# 08C-005.net
KiCad netlist of a schematic drawn in EAGLE
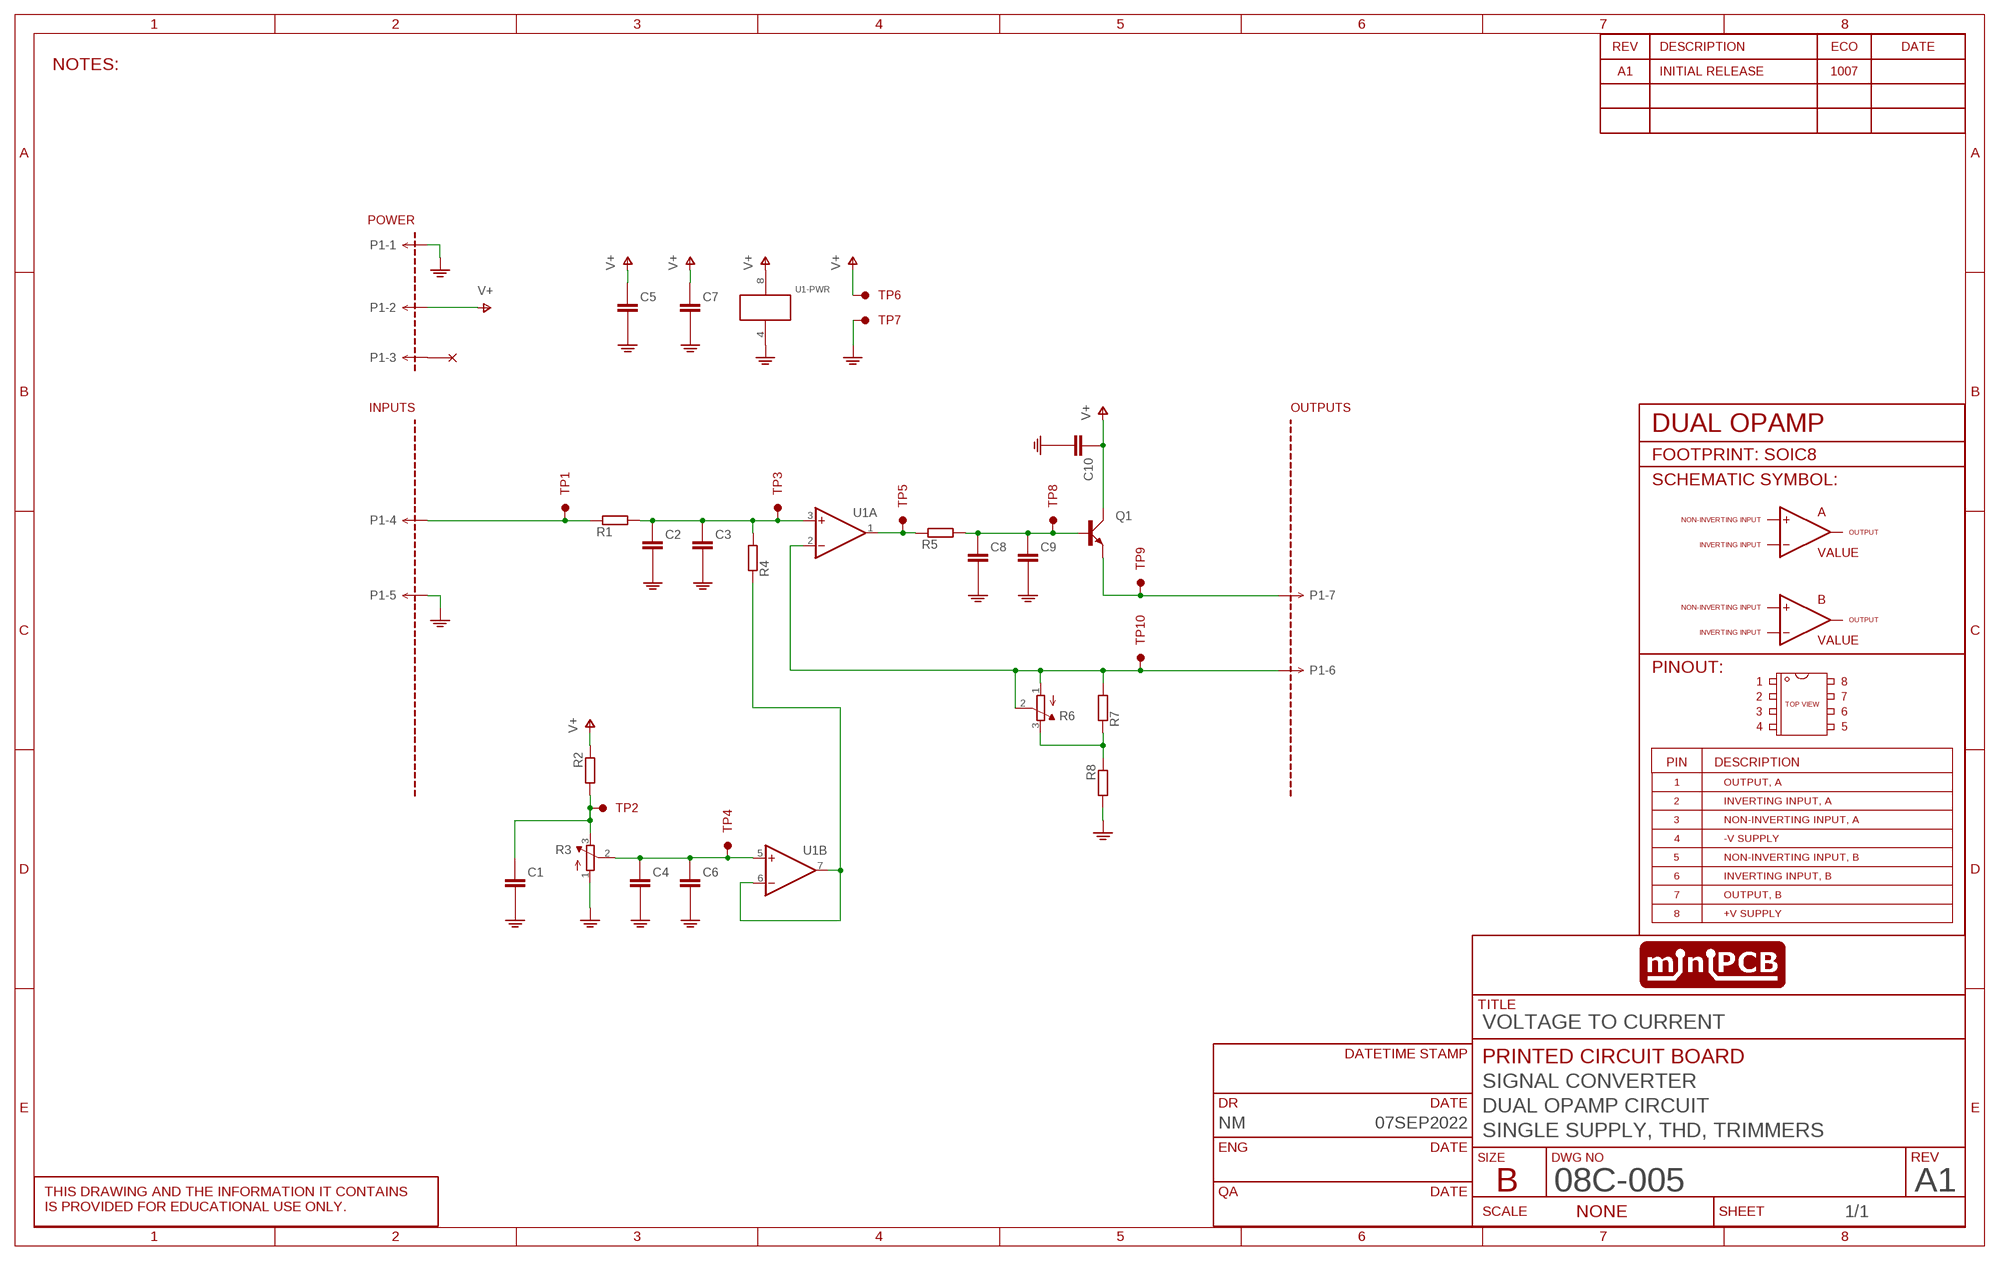
[diagram p0: schematic, sheet 1]

(export (version "E")
  (design (tool "Eeschema 10.0.6"))
  (components
    (comp (ref "C1")
      (value "CAPACITORTHD")
      (footprint "eagle-import:C050-024X044")
      (libsource (lib "eagle-import") (part "CAPACITORTHD"))
    )
    (comp (ref "C2")
      (value "CAPACITORTHD")
      (footprint "eagle-import:C050-024X044")
      (libsource (lib "eagle-import") (part "CAPACITORTHD"))
    )
    (comp (ref "C3")
      (value "CAPACITORTHD")
      (footprint "eagle-import:C050-024X044")
      (libsource (lib "eagle-import") (part "CAPACITORTHD"))
    )
    (comp (ref "C4")
      (value "CAPACITORTHD")
      (footprint "eagle-import:C050-024X044")
      (libsource (lib "eagle-import") (part "CAPACITORTHD"))
    )
    (comp (ref "C5")
      (value "CAPACITORTHD")
      (footprint "eagle-import:C050-024X044")
      (libsource (lib "eagle-import") (part "CAPACITORTHD"))
    )
    (comp (ref "C6")
      (value "CAPACITORTHD")
      (footprint "eagle-import:C050-024X044")
      (libsource (lib "eagle-import") (part "CAPACITORTHD"))
    )
    (comp (ref "C7")
      (value "CAPACITORTHD")
      (footprint "eagle-import:C050-024X044")
      (libsource (lib "eagle-import") (part "CAPACITORTHD"))
    )
    (comp (ref "C8")
      (value "CAPACITORTHD")
      (footprint "eagle-import:C050-024X044")
      (libsource (lib "eagle-import") (part "CAPACITORTHD"))
    )
    (comp (ref "C9")
      (value "CAPACITORTHD")
      (footprint "eagle-import:C050-024X044")
      (libsource (lib "eagle-import") (part "CAPACITORTHD"))
    )
    (comp (ref "C10")
      (value "CAPACITOR_10")
      (footprint "eagle-import:C5MM")
      (libsource (lib "eagle-import") (part "CAPACITOR_10"))
    )
    (comp (ref "P1")
      (value "MINIPCB_7P")
      (footprint "eagle-import:PINS_1X7")
      (libsource (lib "eagle-import") (part "MINIPCB_7P"))
    )
    (comp (ref "PCB1")
      (value "MINIPCB_0P50X50")
      (footprint "eagle-import:MINIPCB_0P_50X50MM")
      (fields
        (field (name "CIRCUIT_CATEGORY") "SIGNAL CONVERTERS")
        (field (name "PART_NUMBER") "08C-005")
        (field (name "REVISION") "A1-01")
        (field (name "TITLE") "VOLTAGE TO CURRENT")
      )
      (libsource (lib "eagle-import") (part "MINIPCB_0P50X50"))
    )
    (comp (ref "Q1")
      (value "BJT_NPNEBC")
      (footprint "eagle-import:TO92-EBC-OVAL")
      (libsource (lib "eagle-import") (part "BJT_NPNEBC"))
    )
    (comp (ref "R1")
      (value "RESISTOR10MM")
      (footprint "eagle-import:0207_10")
      (libsource (lib "eagle-import") (part "RESISTOR10MM"))
    )
    (comp (ref "R2")
      (value "RESISTOR10MM")
      (footprint "eagle-import:0207_10")
      (libsource (lib "eagle-import") (part "RESISTOR10MM"))
    )
    (comp (ref "R3")
      (value "TRIMPOT0.100THD")
      (footprint "eagle-import:TRIM_0100")
      (libsource (lib "eagle-import") (part "TRIMPOT0.100THD"))
    )
    (comp (ref "R4")
      (value "RESISTOR10MM")
      (footprint "eagle-import:0207_10")
      (libsource (lib "eagle-import") (part "RESISTOR10MM"))
    )
    (comp (ref "R5")
      (value "RESISTOR10MM")
      (footprint "eagle-import:0207_10")
      (libsource (lib "eagle-import") (part "RESISTOR10MM"))
    )
    (comp (ref "R6")
      (value "TRIMPOT0.100THD")
      (footprint "eagle-import:TRIM_0100")
      (libsource (lib "eagle-import") (part "TRIMPOT0.100THD"))
    )
    (comp (ref "R7")
      (value "RESISTOR10MM")
      (footprint "eagle-import:0207_10")
      (libsource (lib "eagle-import") (part "RESISTOR10MM"))
    )
    (comp (ref "R8")
      (value "RESISTOR10MM")
      (footprint "eagle-import:0207_10")
      (libsource (lib "eagle-import") (part "RESISTOR10MM"))
    )
    (comp (ref "TP1")
      (value "TESTPOINTKE5000-SMTEXT")
      (footprint "eagle-import:PINS_1_TESTPOINT_KE5000_NOTEXT")
      (libsource (lib "eagle-import") (part "TESTPOINTKE5000-SMTEXT"))
    )
    (comp (ref "TP2")
      (value "TESTPOINTKE5000-SMTEXT")
      (footprint "eagle-import:PINS_1_TESTPOINT_KE5000_NOTEXT")
      (libsource (lib "eagle-import") (part "TESTPOINTKE5000-SMTEXT"))
    )
    (comp (ref "TP3")
      (value "TESTPOINTKE5000-SMTEXT")
      (footprint "eagle-import:PINS_1_TESTPOINT_KE5000_NOTEXT")
      (libsource (lib "eagle-import") (part "TESTPOINTKE5000-SMTEXT"))
    )
    (comp (ref "TP4")
      (value "TESTPOINTKE5000-SMTEXT")
      (footprint "eagle-import:PINS_1_TESTPOINT_KE5000_NOTEXT")
      (libsource (lib "eagle-import") (part "TESTPOINTKE5000-SMTEXT"))
    )
    (comp (ref "TP5")
      (value "TESTPOINTKE5000-SMTEXT")
      (footprint "eagle-import:PINS_1_TESTPOINT_KE5000_NOTEXT")
      (libsource (lib "eagle-import") (part "TESTPOINTKE5000-SMTEXT"))
    )
    (comp (ref "TP6")
      (value "TESTPOINTKE5000-SMTEXT")
      (footprint "eagle-import:PINS_1_TESTPOINT_KE5000_NOTEXT")
      (libsource (lib "eagle-import") (part "TESTPOINTKE5000-SMTEXT"))
    )
    (comp (ref "TP7")
      (value "TESTPOINTKE5000-SMTEXT")
      (footprint "eagle-import:PINS_1_TESTPOINT_KE5000_NOTEXT")
      (libsource (lib "eagle-import") (part "TESTPOINTKE5000-SMTEXT"))
    )
    (comp (ref "TP8")
      (value "TESTPOINTKE5000-SMTEXT")
      (footprint "eagle-import:PINS_1_TESTPOINT_KE5000_NOTEXT")
      (libsource (lib "eagle-import") (part "TESTPOINTKE5000-SMTEXT"))
    )
    (comp (ref "TP9")
      (value "TESTPOINTKE5000-SMTEXT")
      (footprint "eagle-import:PINS_1_TESTPOINT_KE5000_NOTEXT")
      (libsource (lib "eagle-import") (part "TESTPOINTKE5000-SMTEXT"))
    )
    (comp (ref "TP10")
      (value "TESTPOINTKE5000-SMTEXT")
      (footprint "eagle-import:PINS_1_TESTPOINT_KE5000_NOTEXT")
      (libsource (lib "eagle-import") (part "TESTPOINTKE5000-SMTEXT"))
    )
    (comp (ref "U1")
      (value "OPAMP_DUALTHD")
      (footprint "eagle-import:DIL08")
      (libsource (lib "eagle-import") (part "OPAMP_DUALTHD"))
    )
  )
  (nets
    (net (code "1") (name "GND") (class "Default")
      (node (ref "C1") (pin "2") (pinfunction "-_2") (pintype "passive"))
      (node (ref "C10") (pin "-") (pinfunction "-_-") (pintype "passive"))
      (node (ref "C2") (pin "2") (pinfunction "-_2") (pintype "passive"))
      (node (ref "C3") (pin "2") (pinfunction "-_2") (pintype "passive"))
      (node (ref "C4") (pin "2") (pinfunction "-_2") (pintype "passive"))
      (node (ref "C5") (pin "2") (pinfunction "-_2") (pintype "passive"))
      (node (ref "C6") (pin "2") (pinfunction "-_2") (pintype "passive"))
      (node (ref "C7") (pin "2") (pinfunction "-_2") (pintype "passive"))
      (node (ref "C8") (pin "2") (pinfunction "-_2") (pintype "passive"))
      (node (ref "C9") (pin "2") (pinfunction "-_2") (pintype "passive"))
      (node (ref "P1") (pin "1") (pinfunction "1_1") (pintype "bidirectional"))
      (node (ref "P1") (pin "5") (pinfunction "1_5") (pintype "bidirectional"))
      (node (ref "R3") (pin "1") (pinfunction "A_1") (pintype "passive"))
      (node (ref "R8") (pin "2") (pinfunction "2_2") (pintype "passive"))
      (node (ref "TP7") (pin "1") (pinfunction "1_1") (pintype "bidirectional"))
      (node (ref "U1") (pin "4") (pinfunction "V-_4") (pintype "power_in"))
    )
    (net (code "2") (name "Net-(C1-+)") (class "Default")
      (node (ref "C1") (pin "1") (pinfunction "+_1") (pintype "passive"))
      (node (ref "R2") (pin "2") (pinfunction "2_2") (pintype "passive"))
      (node (ref "R3") (pin "3") (pinfunction "E_3") (pintype "passive"))
      (node (ref "TP2") (pin "1") (pinfunction "1_1") (pintype "bidirectional"))
    )
    (net (code "3") (name "Net-(C2-+)") (class "Default")
      (node (ref "C2") (pin "1") (pinfunction "+_1") (pintype "passive"))
      (node (ref "C3") (pin "1") (pinfunction "+_1") (pintype "passive"))
      (node (ref "R1") (pin "2") (pinfunction "2_2") (pintype "passive"))
      (node (ref "R4") (pin "2") (pinfunction "2_2") (pintype "passive"))
      (node (ref "TP3") (pin "1") (pinfunction "1_1") (pintype "bidirectional"))
      (node (ref "U1") (pin "3") (pinfunction "+IN_3") (pintype "input"))
    )
    (net (code "4") (name "Net-(C4-+)") (class "Default")
      (node (ref "C4") (pin "1") (pinfunction "+_1") (pintype "passive"))
      (node (ref "C6") (pin "1") (pinfunction "+_1") (pintype "passive"))
      (node (ref "R3") (pin "2") (pinfunction "S_2") (pintype "passive"))
      (node (ref "TP4") (pin "1") (pinfunction "1_1") (pintype "bidirectional"))
      (node (ref "U1") (pin "5") (pinfunction "+IN_5") (pintype "input"))
    )
    (net (code "5") (name "Net-(C8-+)") (class "Default")
      (node (ref "C8") (pin "1") (pinfunction "+_1") (pintype "passive"))
      (node (ref "C9") (pin "1") (pinfunction "+_1") (pintype "passive"))
      (node (ref "Q1") (pin "B") (pinfunction "B_B") (pintype "passive"))
      (node (ref "R5") (pin "2") (pinfunction "2_2") (pintype "passive"))
      (node (ref "TP8") (pin "1") (pinfunction "1_1") (pintype "bidirectional"))
    )
    (net (code "6") (name "Net-(P1D-1)") (class "Default")
      (node (ref "P1") (pin "4") (pinfunction "1_4") (pintype "bidirectional"))
      (node (ref "R1") (pin "1") (pinfunction "1_1") (pintype "passive"))
      (node (ref "TP1") (pin "1") (pinfunction "1_1") (pintype "bidirectional"))
    )
    (net (code "7") (name "Net-(P1F-1)") (class "Default")
      (node (ref "P1") (pin "6") (pinfunction "1_6") (pintype "bidirectional"))
      (node (ref "R6") (pin "1") (pinfunction "A_1") (pintype "passive"))
      (node (ref "R6") (pin "2") (pinfunction "S_2") (pintype "passive"))
      (node (ref "R7") (pin "2") (pinfunction "2_2") (pintype "passive"))
      (node (ref "TP10") (pin "1") (pinfunction "1_1") (pintype "bidirectional"))
      (node (ref "U1") (pin "2") (pinfunction "-IN_2") (pintype "input"))
    )
    (net (code "8") (name "Net-(P1G-1)") (class "Default")
      (node (ref "P1") (pin "7") (pinfunction "1_7") (pintype "bidirectional"))
      (node (ref "Q1") (pin "E") (pinfunction "E_E") (pintype "passive"))
      (node (ref "TP9") (pin "1") (pinfunction "1_1") (pintype "bidirectional"))
    )
    (net (code "9") (name "Net-(R6-E)") (class "Default")
      (node (ref "R6") (pin "3") (pinfunction "E_3") (pintype "passive"))
      (node (ref "R7") (pin "1") (pinfunction "1_1") (pintype "passive"))
      (node (ref "R8") (pin "1") (pinfunction "1_1") (pintype "passive"))
    )
    (net (code "10") (name "Net-(U1B-OUT)") (class "Default")
      (node (ref "R5") (pin "1") (pinfunction "1_1") (pintype "passive"))
      (node (ref "TP5") (pin "1") (pinfunction "1_1") (pintype "bidirectional"))
      (node (ref "U1") (pin "1") (pinfunction "OUT_1") (pintype "output"))
    )
    (net (code "11") (name "Net-(U1C--IN)") (class "Default")
      (node (ref "R4") (pin "1") (pinfunction "1_1") (pintype "passive"))
      (node (ref "U1") (pin "6") (pinfunction "-IN_6") (pintype "input"))
      (node (ref "U1") (pin "7") (pinfunction "OUT_7") (pintype "output"))
    )
    (net (code "12") (name "V+") (class "Default")
      (node (ref "C10") (pin "+") (pinfunction "+_+") (pintype "passive"))
      (node (ref "C5") (pin "1") (pinfunction "+_1") (pintype "passive"))
      (node (ref "C7") (pin "1") (pinfunction "+_1") (pintype "passive"))
      (node (ref "P1") (pin "2") (pinfunction "1_2") (pintype "bidirectional"))
      (node (ref "Q1") (pin "C") (pinfunction "C_C") (pintype "passive"))
      (node (ref "R2") (pin "1") (pinfunction "1_1") (pintype "passive"))
      (node (ref "TP6") (pin "1") (pinfunction "1_1") (pintype "bidirectional"))
      (node (ref "U1") (pin "8") (pinfunction "V+_8") (pintype "power_in"))
    )
    (net (code "13") (name "unconnected-(P1C-1-Pad3)") (class "Default")
      (node (ref "P1") (pin "3") (pinfunction "1_3") (pintype "bidirectional"))
    )
  )
)
